# NANO-SCH.net
KiCad netlist of a schematic drawn in Altium Designer
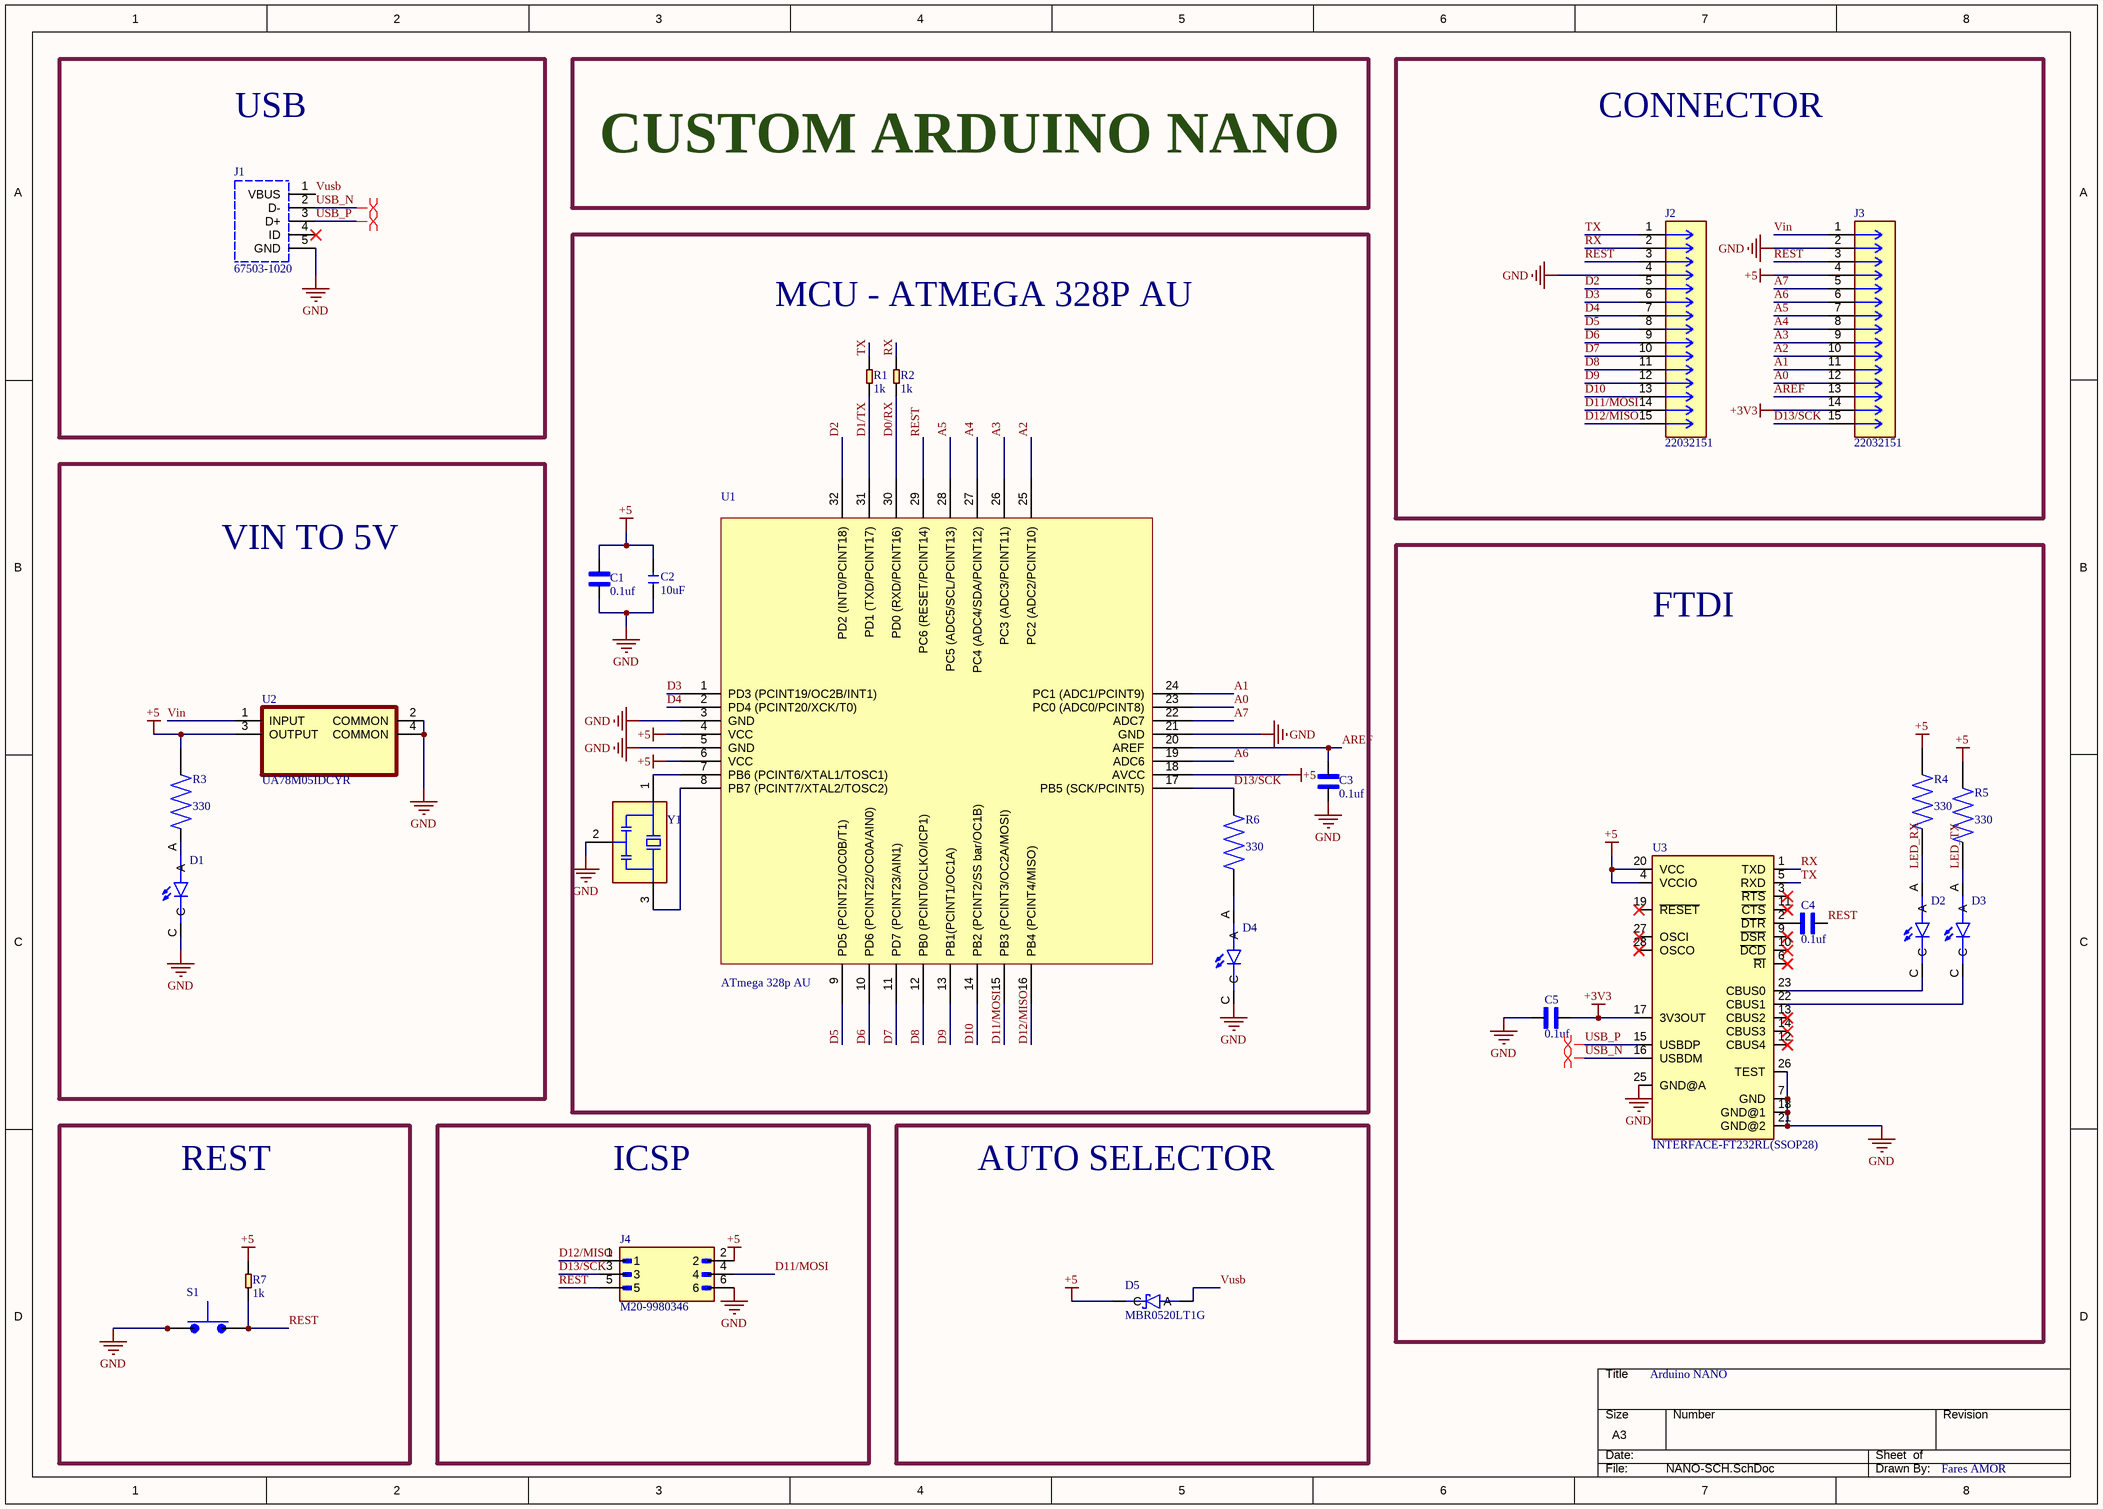
[diagram p0: NANO-SCH.SchDoc]

(export (version "E")
  (design (tool "Eeschema 10.0.6"))
  (components
    (comp (ref "C1")
      (value "0.1uf")
      (footprint "CAPC1005X55N")
      (description "0.1 ÂµF Â±10% 16V Ceramic Capacitor X7R 0402 (1005 Metric)")
      (fields (field (name "MF") "Yageo") (field (name "MP") "CC0402KRX7R7BB104"))
      (libsource (lib "") (part "CC0402KRX7R7BB104_1"))
    )
    (comp (ref "C2")
      (value "10uF")
      (footprint "C0402")
      (description "10 ÂµF Â±20% 6.3V Ceramic Capacitor X5R 0402 (1005 Metric)")
      (fields (field (name "MF") "Yageo") (field (name "MP") "CC0402MRX5R5BB106"))
      (libsource (lib "Schlib") (part "CERAMIC-10UF-6.3V-20%-X5R(0402)"))
    )
    (comp (ref "C3")
      (value "0.1uf")
      (footprint "CAPC1005X55N")
      (description "0.1 ÂµF Â±10% 16V Ceramic Capacitor X7R 0402 (1005 Metric)")
      (fields (field (name "MF") "Yageo") (field (name "MP") "CC0402KRX7R7BB104"))
      (libsource (lib "") (part "CC0402KRX7R7BB104_1"))
    )
    (comp (ref "C4")
      (value "0.1uf")
      (footprint "CAPC1005X55N")
      (description "0.1 ÂµF Â±10% 16V Ceramic Capacitor X7R 0402 (1005 Metric)")
      (fields (field (name "MF") "Yageo") (field (name "MP") "CC0402KRX7R7BB104"))
      (libsource (lib "Schlib") (part "CC0402KRX7R7BB104"))
    )
    (comp (ref "C5")
      (value "0.1uf")
      (footprint "CAPC1005X55N")
      (description "0.1 ÂµF Â±10% 16V Ceramic Capacitor X7R 0402 (1005 Metric)")
      (fields (field (name "MF") "Yageo") (field (name "MP") "CC0402KRX7R7BB104"))
      (libsource (lib "Schlib") (part "CC0402KRX7R7BB104"))
    )
    (comp (ref "D1")
      (value "LTST-C190GKT")
      (footprint "LEDM1608X80")
      (description "Green 1.6 x 0.8 x 0.8 mm 130Â° Water Clear 6 mcd 2.1 V SMT LED")
      (libsource (lib "Schlib") (part "LTST-C190GKT"))
    )
    (comp (ref "D2")
      (value "LTST-C190GKT")
      (footprint "LEDM1608X80")
      (description "Green 1.6 x 0.8 x 0.8 mm 130Â° Water Clear 6 mcd 2.1 V SMT LED")
      (libsource (lib "Schlib") (part "LTST-C190GKT"))
    )
    (comp (ref "D3")
      (value "LTST-C190GKT")
      (footprint "LEDM1608X80")
      (description "Green 1.6 x 0.8 x 0.8 mm 130Â° Water Clear 6 mcd 2.1 V SMT LED")
      (libsource (lib "Schlib") (part "LTST-C190GKT"))
    )
    (comp (ref "D4")
      (value "LTST-C190GKT")
      (footprint "LEDM1608X80")
      (description "Green 1.6 x 0.8 x 0.8 mm 130Â° Water Clear 6 mcd 2.1 V SMT LED")
      (libsource (lib "Schlib") (part "LTST-C190GKT"))
    )
    (comp (ref "D5")
      (value "MBR0520LT1G")
      (footprint "SOD3716X135N")
      (description "Diode Schottky 20 V 500mA Surface Mount SOD-123")
      (fields (field (name "MF") "ON Semiconductor"))
      (libsource (lib "Schlib") (part "MBR0520LT1G"))
    )
    (comp (ref "J1")
      (value "67503-1020")
      (footprint "67503-1020")
      (fields (field (name "MF") "Molex"))
      (libsource (lib "Schlib") (part "67503-1020"))
    )
    (comp (ref "J2")
      (value "22032151")
      (footprint "CONN15X1_22032151_MOL")
      (libsource (lib "Schlib") (part "22032151"))
    )
    (comp (ref "J3")
      (value "22032151")
      (footprint "CONN15X1_22032151_MOL")
      (libsource (lib "Schlib") (part "22032151"))
    )
    (comp (ref "J4")
      (value "M20-9980346")
      (footprint "HARWIN_M20-9980346")
      (libsource (lib "Schlib") (part "M20-9980346"))
    )
    (comp (ref "R1")
      (value "1k")
      (footprint "R0402")
      (description "301010006")
      (fields (field (name "MF") "{'manufacturer': u'YAGEO'}") (field (name "MP") "RC0402JR-071KL"))
      (libsource (lib "Schlib") (part "SMD-RES-1K-5%-1/16W(0402)"))
    )
    (comp (ref "R2")
      (value "1k")
      (footprint "R0402")
      (description "301010006")
      (fields (field (name "MF") "{'manufacturer': u'YAGEO'}") (field (name "MP") "RC0402JR-071KL"))
      (libsource (lib "Schlib") (part "SMD-RES-1K-5%-1/16W(0402)"))
    )
    (comp (ref "R3")
      (value "330")
      (footprint "RESC1005X35N")
      (description "330 Ohms Â±0.1% 0.063W, 1/16W Chip Resistor 0402 (1005 Metric) Thin Film")
      (fields (field (name "MF") "Yageo") (field (name "MP") "RT0402BRD07330RL"))
      (libsource (lib "Schlib") (part "RT0402BRD07330RL"))
    )
    (comp (ref "R4")
      (value "330")
      (footprint "RESC1005X35N")
      (description "330 Ohms Â±0.1% 0.063W, 1/16W Chip Resistor 0402 (1005 Metric) Thin Film")
      (fields (field (name "MF") "Yageo") (field (name "MP") "RT0402BRD07330RL"))
      (libsource (lib "Schlib") (part "RT0402BRD07330RL"))
    )
    (comp (ref "R5")
      (value "330")
      (footprint "RESC1005X35N")
      (description "330 Ohms Â±0.1% 0.063W, 1/16W Chip Resistor 0402 (1005 Metric) Thin Film")
      (fields (field (name "MF") "Yageo") (field (name "MP") "RT0402BRD07330RL"))
      (libsource (lib "Schlib") (part "RT0402BRD07330RL"))
    )
    (comp (ref "R6")
      (value "330")
      (footprint "RESC1005X35N")
      (description "330 Ohms Â±0.1% 0.063W, 1/16W Chip Resistor 0402 (1005 Metric) Thin Film")
      (fields (field (name "MF") "Yageo") (field (name "MP") "RT0402BRD07330RL"))
      (libsource (lib "Schlib") (part "RT0402BRD07330RL"))
    )
    (comp (ref "R7")
      (value "1k")
      (footprint "R0402")
      (description "301010006")
      (fields (field (name "MF") "{'manufacturer': u'YAGEO'}") (field (name "MP") "RC0402JR-071KL"))
      (libsource (lib "Schlib") (part "SMD-RES-1K-5%-1/16W(0402)"))
    )
    (comp (ref "S1")
      (value "SKRPABE010")
      (footprint "SW_SKRPABE010")
      (description "Switch Tactile N.O. SPST Button J-Bend 0.05A 16VDC 1.57N SMD Automotive T/R")
      (fields (field (name "MF") "ALPS"))
      (libsource (lib "Schlib") (part "SKRPABE010"))
    )
    (comp (ref "U1")
      (value "ATmega 328p AU")
      (footprint "ATmega328P")
      (libsource (lib "Schlib") (part "ATmega328p"))
    )
    (comp (ref "U2")
      (value "UA78M05IDCYR")
      (footprint "SOT230P700X180-4N")
      (description "500-mA, 30-V, linear voltage regulator")
      (fields (field (name "MF") "Texas Instruments"))
      (libsource (lib "Schlib") (part "UA78M05IDCYR"))
    )
    (comp (ref "U3")
      (value "INTERFACE-FT232RL(SSOP28)")
      (footprint "SSOP28-0.65-10.2X5.2MM")
      (description "USB-Ð¼Ð¾ÑÑ‚, Ð¸Ð½Ñ‚ÐµÑ€Ñ„ÐµÐ¹Ñ USB Ðº UART USB 2.0 UART 28-SSOP")
      (fields (field (name "MP") "FT232RL") (field (name "MF") "FTDI, Future"))
      (libsource (lib "Schlib") (part "INTERFACE-FT232RL(SSOP28)"))
    )
    (comp (ref "Y1")
      (value "CSTCE16M0V53-R0")
      (footprint "OSC_CSTCE16M0V53-R0")
      (description "16 MHz Ceramic Resonator Built in Capacitor 15 pF Â±0.3% -20Â°C ~ 80Â°C Surface Mount")
      (fields (field (name "MF") "Murata") (field (name "MP") "CSTCE16M0V53-R0-"))
      (libsource (lib "Schlib") (part "CSTCE16M0V53-R0"))
    )
  )
  (nets
    (net (code "1") (name "+3V3") (class "Default")
      (node (ref "C5") (pin "1") (pinfunction "1_1") (pintype "passive"))
      (node (ref "J3") (pin "14") (pinfunction "14_14") (pintype "passive"))
      (node (ref "U3") (pin "17") (pinfunction "3V3OUT_17") (pintype "passive"))
    )
    (net (code "2") (name "+5") (class "Default")
      (node (ref "C1") (pin "1") (pinfunction "1_1") (pintype "passive"))
      (node (ref "C2") (pin "2") (pinfunction "2_2") (pintype "passive"))
      (node (ref "D5") (pin "C") (pinfunction "C_C") (pintype "passive"))
      (node (ref "J3") (pin "4") (pinfunction "4_4") (pintype "passive"))
      (node (ref "J4") (pin "2") (pinfunction "2_2") (pintype "passive"))
      (node (ref "R3") (pin "2") (pinfunction "2_2") (pintype "passive"))
      (node (ref "R4") (pin "2") (pinfunction "2_2") (pintype "passive"))
      (node (ref "R5") (pin "2") (pinfunction "2_2") (pintype "passive"))
      (node (ref "R7") (pin "2") (pinfunction "2_2") (pintype "passive"))
      (node (ref "U1") (pin "18") (pinfunction "AVCC_18") (pintype "passive"))
      (node (ref "U1") (pin "4") (pinfunction "VCC_4") (pintype "passive"))
      (node (ref "U1") (pin "6") (pinfunction "VCC_6") (pintype "passive"))
      (node (ref "U2") (pin "3") (pinfunction "OUTPUT_3") (pintype "passive"))
      (node (ref "U3") (pin "20") (pinfunction "VCC_20") (pintype "passive"))
      (node (ref "U3") (pin "4") (pinfunction "VCCIO_4") (pintype "passive"))
    )
    (net (code "3") (name "/A0") (class "Default")
      (node (ref "J3") (pin "12") (pinfunction "12_12") (pintype "passive"))
      (node (ref "U1") (pin "23") (pinfunction "PC0_(ADC0/PCINT8)_23") (pintype "passive"))
    )
    (net (code "4") (name "/A1") (class "Default")
      (node (ref "J3") (pin "11") (pinfunction "11_11") (pintype "passive"))
      (node (ref "U1") (pin "24") (pinfunction "PC1_(ADC1/PCINT9)_24") (pintype "passive"))
    )
    (net (code "5") (name "/A2") (class "Default")
      (node (ref "J3") (pin "10") (pinfunction "10_10") (pintype "passive"))
      (node (ref "U1") (pin "25") (pinfunction "PC2_(ADC2/PCINT10)_25") (pintype "passive"))
    )
    (net (code "6") (name "/A3") (class "Default")
      (node (ref "J3") (pin "9") (pinfunction "9_9") (pintype "passive"))
      (node (ref "U1") (pin "26") (pinfunction "PC3_(ADC3/PCINT11)_26") (pintype "passive"))
    )
    (net (code "7") (name "/A4") (class "Default")
      (node (ref "J3") (pin "8") (pinfunction "8_8") (pintype "passive"))
      (node (ref "U1") (pin "27") (pinfunction "PC4_(ADC4/SDA/PCINT12)_27") (pintype "passive"))
    )
    (net (code "8") (name "/A5") (class "Default")
      (node (ref "J3") (pin "7") (pinfunction "7_7") (pintype "passive"))
      (node (ref "U1") (pin "28") (pinfunction "PC5_(ADC5/SCL/PCINT13)_28") (pintype "passive"))
    )
    (net (code "9") (name "/A6") (class "Default")
      (node (ref "J3") (pin "6") (pinfunction "6_6") (pintype "passive"))
      (node (ref "U1") (pin "19") (pinfunction "ADC6_19") (pintype "passive"))
    )
    (net (code "10") (name "/A7") (class "Default")
      (node (ref "J3") (pin "5") (pinfunction "5_5") (pintype "passive"))
      (node (ref "U1") (pin "22") (pinfunction "ADC7_22") (pintype "passive"))
    )
    (net (code "11") (name "/AREF") (class "Default")
      (node (ref "C3") (pin "1") (pinfunction "1_1") (pintype "passive"))
      (node (ref "J3") (pin "13") (pinfunction "13_13") (pintype "passive"))
      (node (ref "U1") (pin "20") (pinfunction "AREF_20") (pintype "passive"))
    )
    (net (code "12") (name "/D0{slash}RX") (class "Default")
      (node (ref "R2") (pin "1") (pinfunction "1_1") (pintype "passive"))
      (node (ref "U1") (pin "30") (pinfunction "PD0_(RXD/PCINT16)_30") (pintype "passive"))
    )
    (net (code "13") (name "/D1{slash}TX") (class "Default")
      (node (ref "R1") (pin "1") (pinfunction "1_1") (pintype "passive"))
      (node (ref "U1") (pin "31") (pinfunction "PD1_(TXD/PCINT17)_31") (pintype "passive"))
    )
    (net (code "14") (name "/D2") (class "Default")
      (node (ref "J2") (pin "5") (pinfunction "5_5") (pintype "passive"))
      (node (ref "U1") (pin "32") (pinfunction "PD2_(INT0/PCINT18)_32") (pintype "passive"))
    )
    (net (code "15") (name "/D3") (class "Default")
      (node (ref "J2") (pin "6") (pinfunction "6_6") (pintype "passive"))
      (node (ref "U1") (pin "1") (pinfunction "PD3_(PCINT19/OC2B/INT1)_1") (pintype "passive"))
    )
    (net (code "16") (name "/D4") (class "Default")
      (node (ref "J2") (pin "7") (pinfunction "7_7") (pintype "passive"))
      (node (ref "U1") (pin "2") (pinfunction "PD4_(PCINT20/XCK/T0)_2") (pintype "passive"))
    )
    (net (code "17") (name "/D5") (class "Default")
      (node (ref "J2") (pin "8") (pinfunction "8_8") (pintype "passive"))
      (node (ref "U1") (pin "9") (pinfunction "PD5_(PCINT21/OC0B/T1)_9") (pintype "passive"))
    )
    (net (code "18") (name "/D6") (class "Default")
      (node (ref "J2") (pin "9") (pinfunction "9_9") (pintype "passive"))
      (node (ref "U1") (pin "10") (pinfunction "PD6_(PCINT22/OC0A/AIN0)_10") (pintype "passive"))
    )
    (net (code "19") (name "/D7") (class "Default")
      (node (ref "J2") (pin "10") (pinfunction "10_10") (pintype "passive"))
      (node (ref "U1") (pin "11") (pinfunction "PD7_(PCINT23/AIN1)_11") (pintype "passive"))
    )
    (net (code "20") (name "/D8") (class "Default")
      (node (ref "J2") (pin "11") (pinfunction "11_11") (pintype "passive"))
      (node (ref "U1") (pin "12") (pinfunction "PB0_(PCINT0/CLKO/ICP1)_12") (pintype "passive"))
    )
    (net (code "21") (name "/D9") (class "Default")
      (node (ref "J2") (pin "12") (pinfunction "12_12") (pintype "passive"))
      (node (ref "U1") (pin "13") (pinfunction "PB1(PCINT1/OC1A)_13") (pintype "passive"))
    )
    (net (code "22") (name "/D10") (class "Default")
      (node (ref "J2") (pin "13") (pinfunction "13_13") (pintype "passive"))
      (node (ref "U1") (pin "14") (pinfunction "PB2_(PCINT2/SS_bar/OC1B)_14") (pintype "passive"))
    )
    (net (code "23") (name "/D11{slash}MOSI") (class "Default")
      (node (ref "J2") (pin "14") (pinfunction "14_14") (pintype "passive"))
      (node (ref "J4") (pin "4") (pinfunction "4_4") (pintype "passive"))
      (node (ref "U1") (pin "15") (pinfunction "PB3_(PCINT3/OC2A/MOSI)_15") (pintype "passive"))
    )
    (net (code "24") (name "/D12{slash}MISO") (class "Default")
      (node (ref "J2") (pin "15") (pinfunction "15_15") (pintype "passive"))
      (node (ref "J4") (pin "1") (pinfunction "1_1") (pintype "passive"))
      (node (ref "U1") (pin "16") (pinfunction "PB4_(PCINT4/MISO)_16") (pintype "passive"))
    )
    (net (code "25") (name "/D13{slash}SCK") (class "Default")
      (node (ref "J3") (pin "15") (pinfunction "15_15") (pintype "passive"))
      (node (ref "J4") (pin "3") (pinfunction "3_3") (pintype "passive"))
      (node (ref "R6") (pin "2") (pinfunction "2_2") (pintype "passive"))
      (node (ref "U1") (pin "17") (pinfunction "PB5_(SCK/PCINT5)_17") (pintype "passive"))
    )
    (net (code "26") (name "/LED_RX") (class "Default")
      (node (ref "D2") (pin "A") (pinfunction "A_A") (pintype "passive"))
      (node (ref "R4") (pin "1") (pinfunction "1_1") (pintype "passive"))
    )
    (net (code "27") (name "/LED_TX") (class "Default")
      (node (ref "D3") (pin "A") (pinfunction "A_A") (pintype "passive"))
      (node (ref "R5") (pin "1") (pinfunction "1_1") (pintype "passive"))
    )
    (net (code "28") (name "/REST") (class "Default")
      (node (ref "C4") (pin "1") (pinfunction "1_1") (pintype "passive"))
      (node (ref "J2") (pin "3") (pinfunction "3_3") (pintype "passive"))
      (node (ref "J3") (pin "3") (pinfunction "3_3") (pintype "passive"))
      (node (ref "J4") (pin "5") (pinfunction "5_5") (pintype "passive"))
      (node (ref "R7") (pin "1") (pinfunction "1_1") (pintype "passive"))
      (node (ref "S1") (pin "3") (pinfunction "2_3") (pintype "passive"))
      (node (ref "S1") (pin "4") (pinfunction "2_4") (pintype "passive"))
      (node (ref "U1") (pin "29") (pinfunction "PC6_(RESET/PCINT14)_29") (pintype "passive"))
    )
    (net (code "29") (name "/RX") (class "Default")
      (node (ref "J2") (pin "2") (pinfunction "2_2") (pintype "passive"))
      (node (ref "R2") (pin "2") (pinfunction "2_2") (pintype "passive"))
      (node (ref "U3") (pin "1") (pinfunction "TXD_1") (pintype "passive"))
    )
    (net (code "30") (name "/TX") (class "Default")
      (node (ref "J2") (pin "1") (pinfunction "1_1") (pintype "passive"))
      (node (ref "R1") (pin "2") (pinfunction "2_2") (pintype "passive"))
      (node (ref "U3") (pin "5") (pinfunction "RXD_5") (pintype "passive"))
    )
    (net (code "31") (name "/USB_N") (class "Default")
      (node (ref "J1") (pin "2") (pinfunction "D-_2") (pintype "passive"))
      (node (ref "U3") (pin "16") (pinfunction "USBDM_16") (pintype "passive"))
    )
    (net (code "32") (name "/USB_P") (class "Default")
      (node (ref "J1") (pin "3") (pinfunction "D+_3") (pintype "passive"))
      (node (ref "U3") (pin "15") (pinfunction "USBDP_15") (pintype "passive"))
    )
    (net (code "33") (name "/Vin") (class "Default")
      (node (ref "J3") (pin "1") (pinfunction "1_1") (pintype "passive"))
      (node (ref "U2") (pin "1") (pinfunction "INPUT_1") (pintype "passive"))
    )
    (net (code "34") (name "/Vusb") (class "Default")
      (node (ref "D5") (pin "A") (pinfunction "A_A") (pintype "passive"))
      (node (ref "J1") (pin "1") (pinfunction "VBUS_1") (pintype "passive"))
    )
    (net (code "35") (name "GND") (class "Default")
      (node (ref "C1") (pin "2") (pinfunction "2_2") (pintype "passive"))
      (node (ref "C2") (pin "1") (pinfunction "1_1") (pintype "passive"))
      (node (ref "C3") (pin "2") (pinfunction "2_2") (pintype "passive"))
      (node (ref "C5") (pin "2") (pinfunction "2_2") (pintype "passive"))
      (node (ref "D1") (pin "C") (pinfunction "C_C") (pintype "passive"))
      (node (ref "D4") (pin "C") (pinfunction "C_C") (pintype "passive"))
      (node (ref "J1") (pin "5") (pinfunction "GND_5") (pintype "passive"))
      (node (ref "J2") (pin "4") (pinfunction "4_4") (pintype "passive"))
      (node (ref "J3") (pin "2") (pinfunction "2_2") (pintype "passive"))
      (node (ref "J4") (pin "6") (pinfunction "6_6") (pintype "passive"))
      (node (ref "S1") (pin "1") (pinfunction "1_1") (pintype "passive"))
      (node (ref "S1") (pin "2") (pinfunction "1_2") (pintype "passive"))
      (node (ref "U1") (pin "21") (pinfunction "GND_21") (pintype "passive"))
      (node (ref "U1") (pin "3") (pinfunction "GND_3") (pintype "passive"))
      (node (ref "U1") (pin "5") (pinfunction "GND_5") (pintype "passive"))
      (node (ref "U2") (pin "2") (pinfunction "COMMON_2") (pintype "passive"))
      (node (ref "U2") (pin "4") (pinfunction "COMMON_4") (pintype "passive"))
      (node (ref "U3") (pin "18") (pinfunction "GND@1_18") (pintype "passive"))
      (node (ref "U3") (pin "21") (pinfunction "GND@2_21") (pintype "passive"))
      (node (ref "U3") (pin "25") (pinfunction "GND@A_25") (pintype "passive"))
      (node (ref "U3") (pin "26") (pinfunction "TEST_26") (pintype "passive"))
      (node (ref "U3") (pin "7") (pinfunction "GND_7") (pintype "passive"))
      (node (ref "Y1") (pin "2") (pinfunction "GND_2") (pintype "power_in"))
    )
    (net (code "36") (name "Net-(D1-PadA)") (class "Default")
      (node (ref "D1") (pin "A") (pinfunction "A_A") (pintype "passive"))
      (node (ref "R3") (pin "1") (pinfunction "1_1") (pintype "passive"))
    )
    (net (code "37") (name "Net-(D4-PadA)") (class "Default")
      (node (ref "D4") (pin "A") (pinfunction "A_A") (pintype "passive"))
      (node (ref "R6") (pin "1") (pinfunction "1_1") (pintype "passive"))
    )
    (net (code "38") (name "Net-(U1-PB6_(PCINT6{slash}XTAL1{slash}TOSC1))") (class "Default")
      (node (ref "U1") (pin "7") (pinfunction "PB6_(PCINT6/XTAL1/TOSC1)_7") (pintype "passive"))
      (node (ref "Y1") (pin "1") (pinfunction "IN_1") (pintype "passive"))
    )
    (net (code "39") (name "Net-(U1-PB7_(PCINT7{slash}XTAL2{slash}TOSC2))") (class "Default")
      (node (ref "U1") (pin "8") (pinfunction "PB7_(PCINT7/XTAL2/TOSC2)_8") (pintype "passive"))
      (node (ref "Y1") (pin "3") (pinfunction "OUT_3") (pintype "passive"))
    )
    (net (code "40") (name "Net-(U3-CBUS0)") (class "Default")
      (node (ref "D2") (pin "C") (pinfunction "C_C") (pintype "passive"))
      (node (ref "U3") (pin "23") (pinfunction "CBUS0_23") (pintype "passive"))
    )
    (net (code "41") (name "Net-(U3-CBUS1)") (class "Default")
      (node (ref "D3") (pin "C") (pinfunction "C_C") (pintype "passive"))
      (node (ref "U3") (pin "22") (pinfunction "CBUS1_22") (pintype "passive"))
    )
    (net (code "42") (name "Net-(U3-~{DTR})") (class "Default")
      (node (ref "C4") (pin "2") (pinfunction "2_2") (pintype "passive"))
      (node (ref "U3") (pin "2") (pinfunction "~{DTR}_2") (pintype "passive"))
    )
    (net (code "43") (name "unconnected-(J1-ID-Pad4)") (class "Default")
      (node (ref "J1") (pin "4") (pinfunction "ID_4") (pintype "passive+no_connect"))
    )
    (net (code "44") (name "unconnected-(U3-CBUS2-Pad13)") (class "Default")
      (node (ref "U3") (pin "13") (pinfunction "CBUS2_13") (pintype "passive+no_connect"))
    )
    (net (code "45") (name "unconnected-(U3-CBUS3-Pad14)") (class "Default")
      (node (ref "U3") (pin "14") (pinfunction "CBUS3_14") (pintype "passive+no_connect"))
    )
    (net (code "46") (name "unconnected-(U3-CBUS4-Pad12)") (class "Default")
      (node (ref "U3") (pin "12") (pinfunction "CBUS4_12") (pintype "passive+no_connect"))
    )
    (net (code "47") (name "unconnected-(U3-OSCI-Pad27)") (class "Default")
      (node (ref "U3") (pin "27") (pinfunction "OSCI_27") (pintype "passive+no_connect"))
    )
    (net (code "48") (name "unconnected-(U3-OSCO-Pad28)") (class "Default")
      (node (ref "U3") (pin "28") (pinfunction "OSCO_28") (pintype "passive+no_connect"))
    )
    (net (code "49") (name "unconnected-(U3-~{CTS}-Pad11)") (class "Default")
      (node (ref "U3") (pin "11") (pinfunction "~{CTS}_11") (pintype "passive+no_connect"))
    )
    (net (code "50") (name "unconnected-(U3-~{DCD}-Pad10)") (class "Default")
      (node (ref "U3") (pin "10") (pinfunction "~{DCD}_10") (pintype "passive+no_connect"))
    )
    (net (code "51") (name "unconnected-(U3-~{DSR}-Pad9)") (class "Default")
      (node (ref "U3") (pin "9") (pinfunction "~{DSR}_9") (pintype "passive+no_connect"))
    )
    (net (code "52") (name "unconnected-(U3-~{RESET}-Pad19)") (class "Default")
      (node (ref "U3") (pin "19") (pinfunction "~{RESET}_19") (pintype "passive+no_connect"))
    )
    (net (code "53") (name "unconnected-(U3-~{RI}-Pad6)") (class "Default")
      (node (ref "U3") (pin "6") (pinfunction "~{RI}_6") (pintype "passive+no_connect"))
    )
    (net (code "54") (name "unconnected-(U3-~{RTS}-Pad3)") (class "Default")
      (node (ref "U3") (pin "3") (pinfunction "~{RTS}_3") (pintype "passive+no_connect"))
    )
  )
)
